# esp32_final.net
KiCad netlist of a schematic drawn in EasyEDA Pro
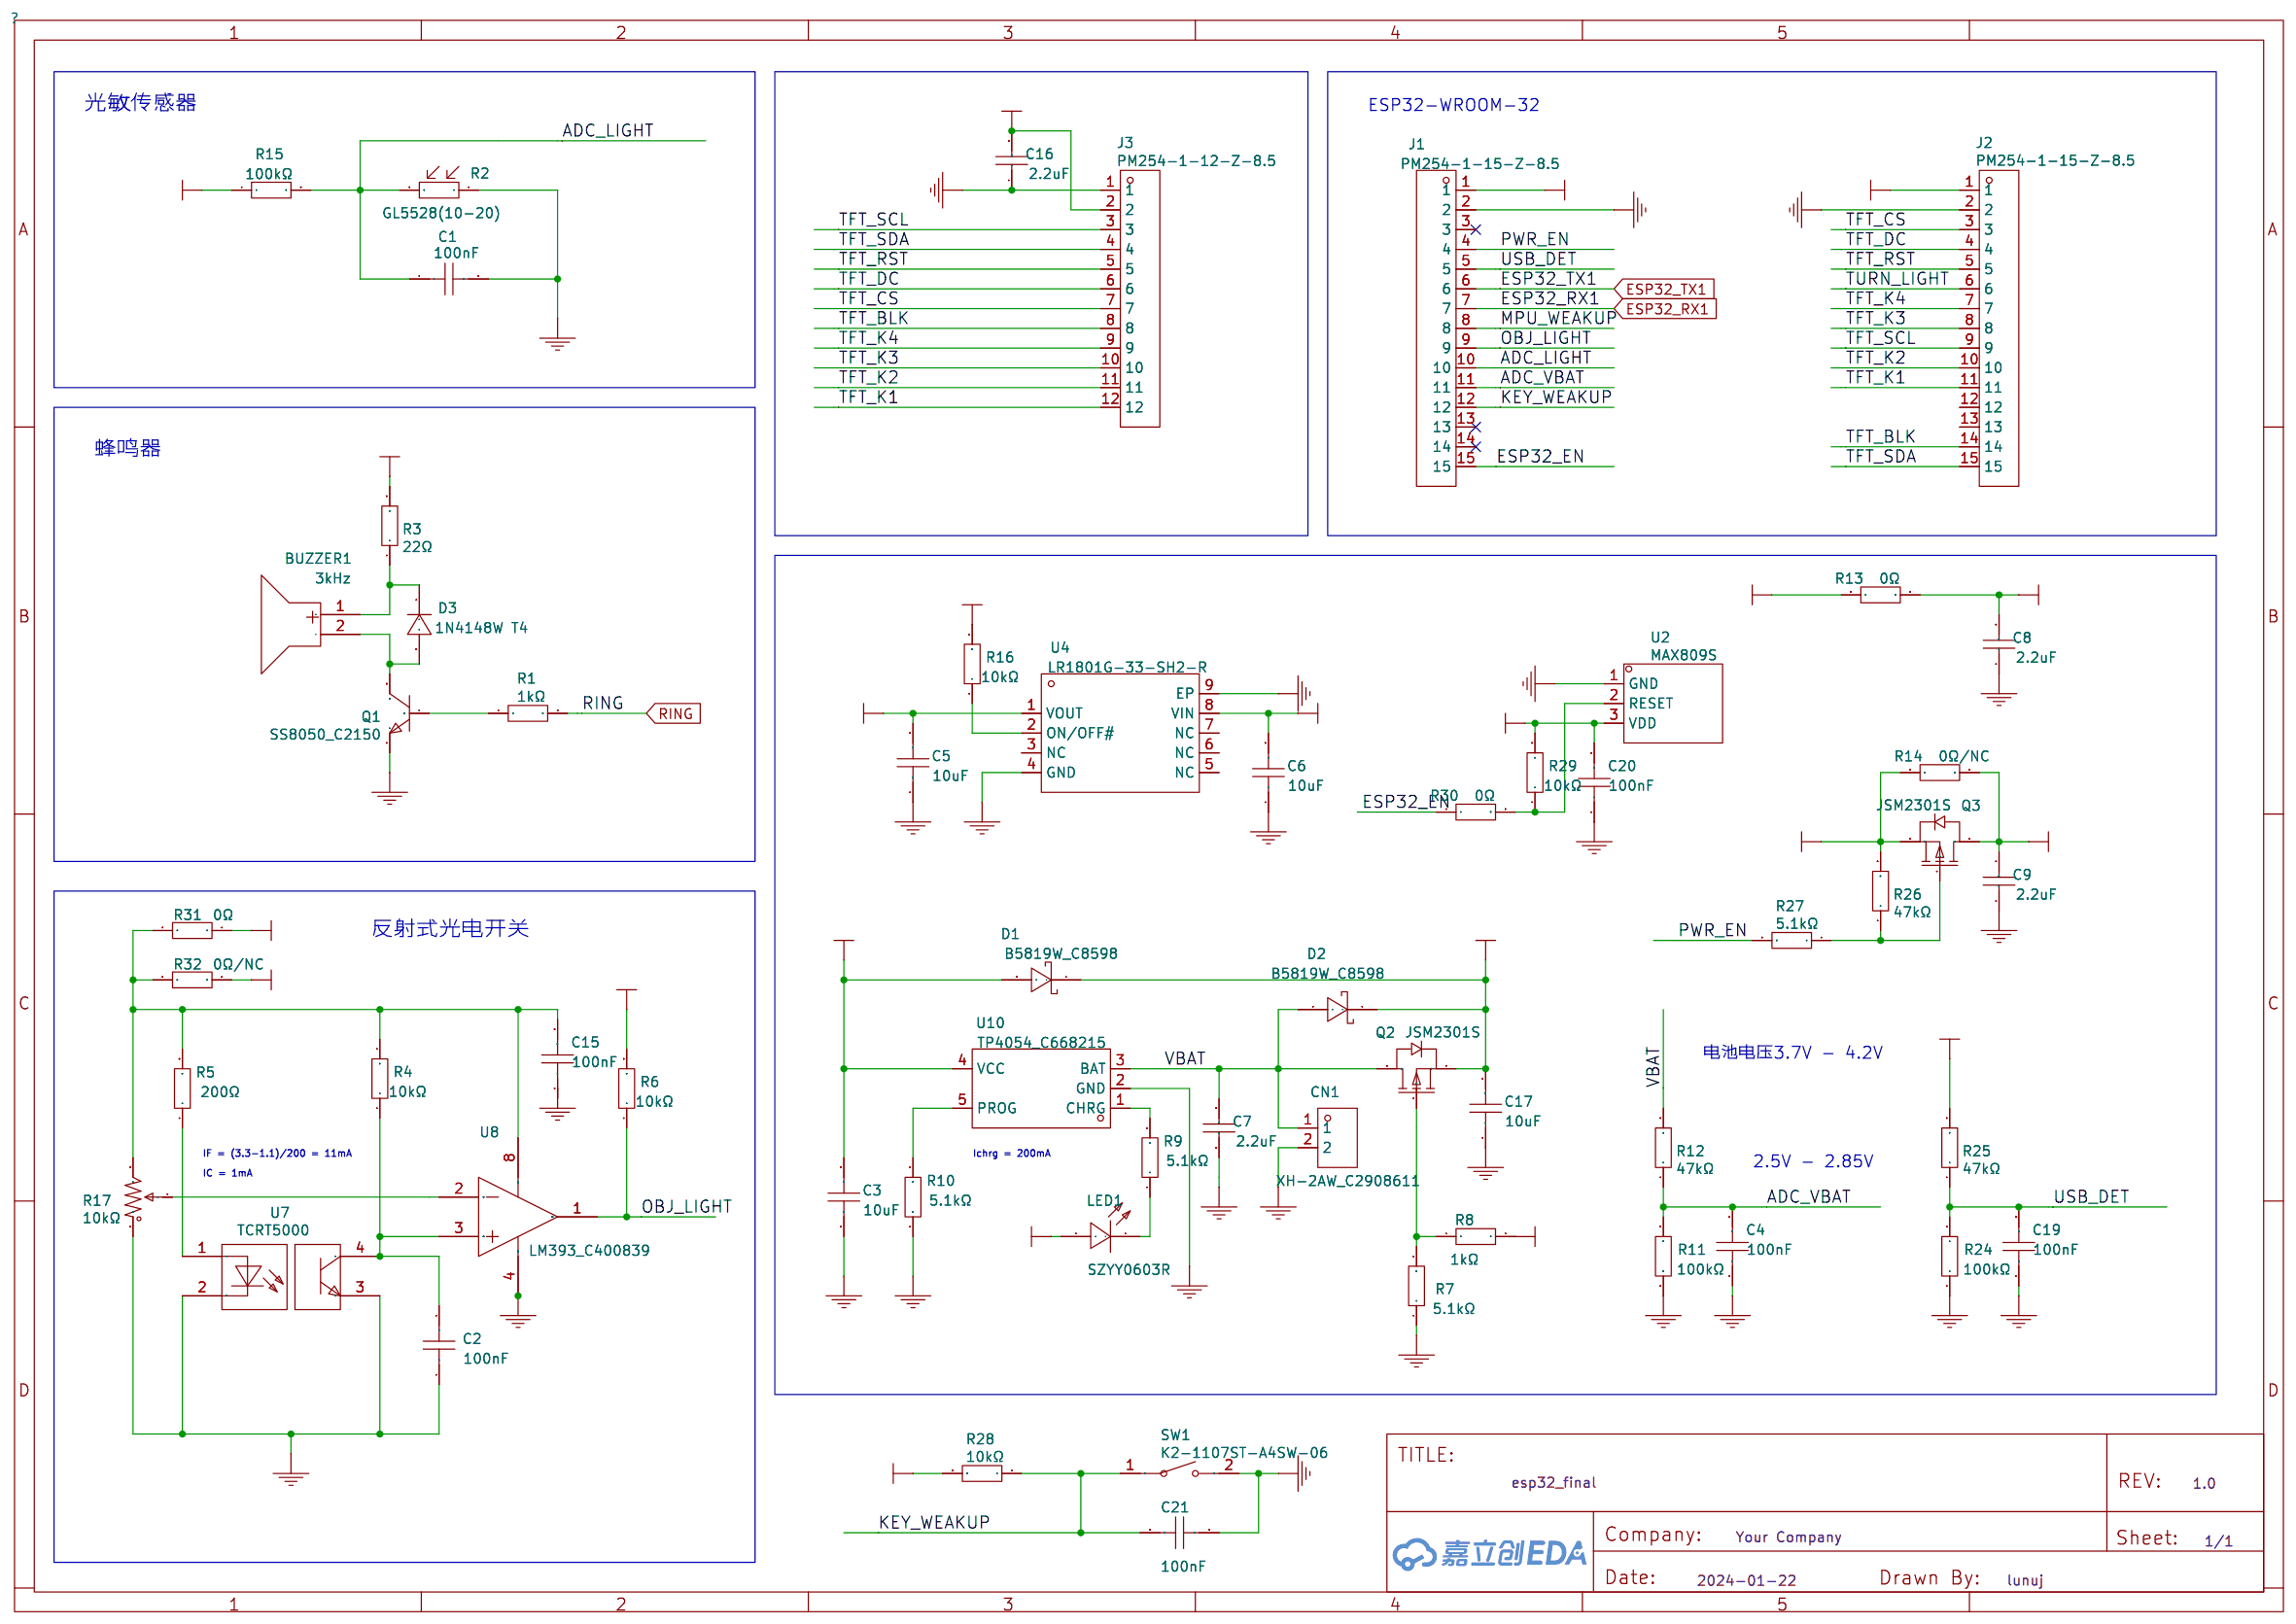
[diagram p0: ESP32]
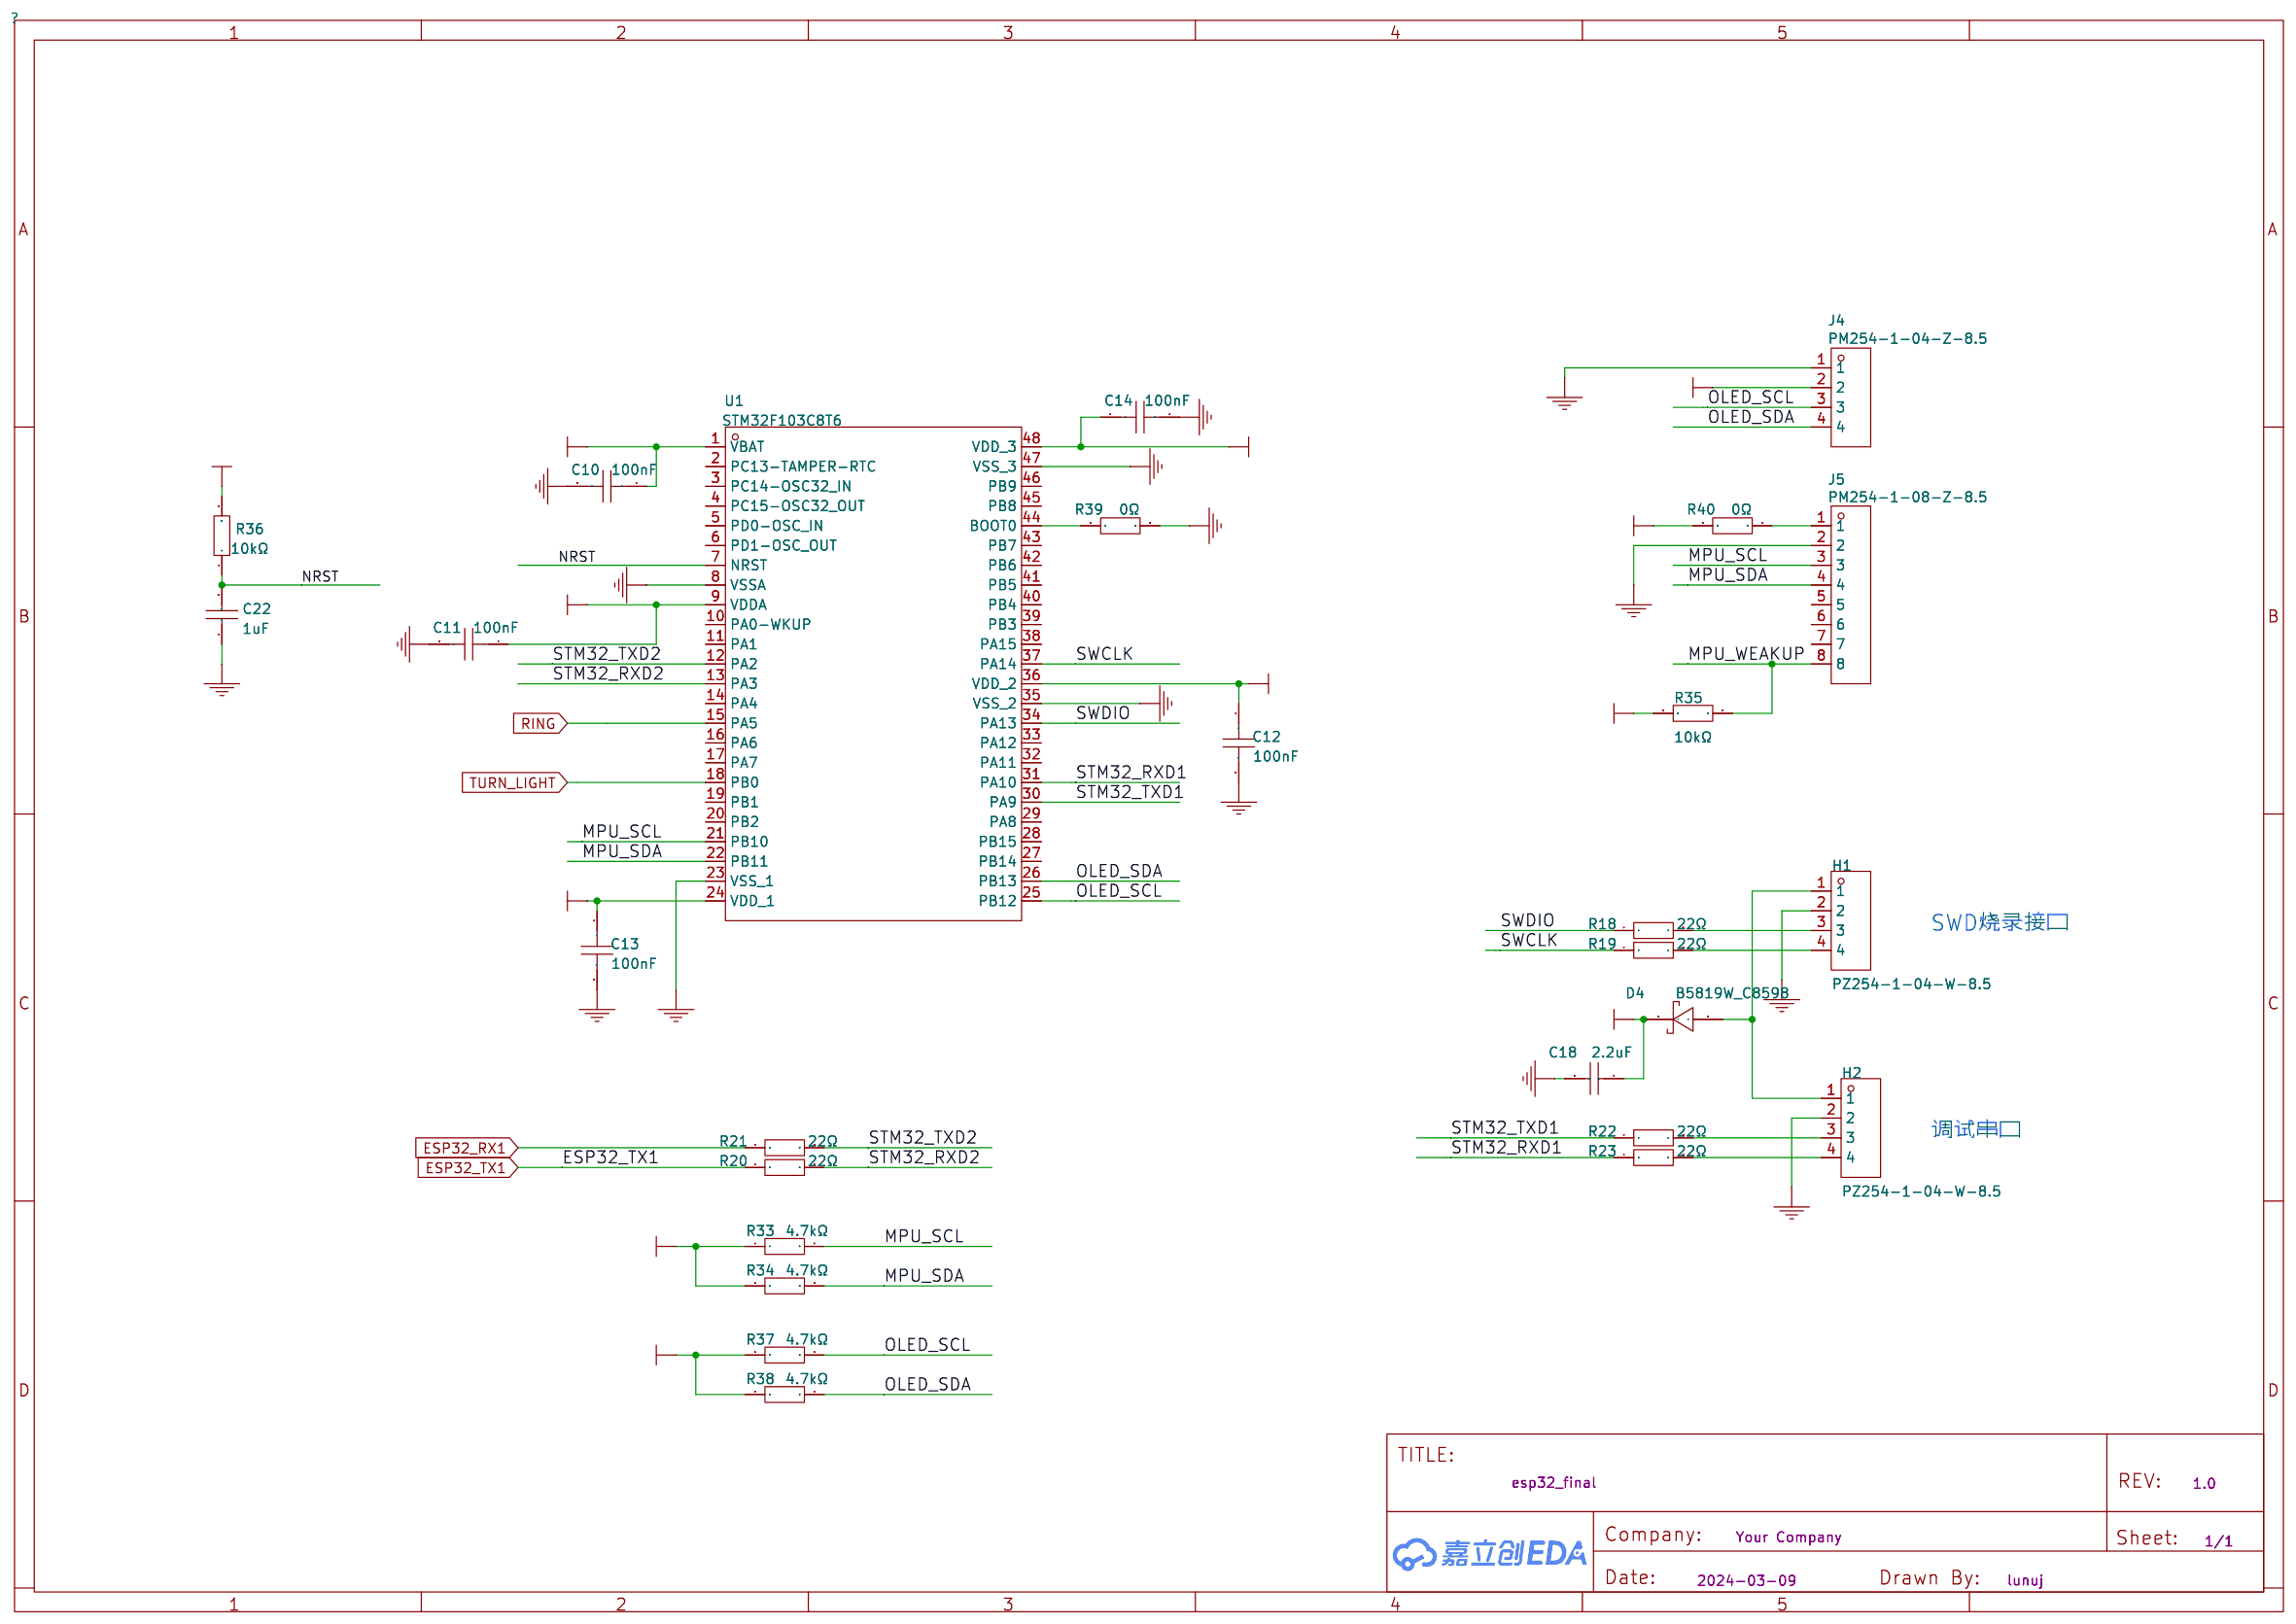
[diagram p1: STM32]

(export (version "E")
  (design (tool "Eeschema 10.0.6"))
  (components
    (comp (ref "BUZZER1")
      (value "3kHz")
      (footprint "easyedapro:footprint_b725")
      (fields (field (name "Manufacturer Part") "HNB09A03") (field (name "Manufacturer") "华能"))
      (libsource (lib "easyedapro") (part "3kHz"))
    )
    (comp (ref "C1")
      (value "100nF")
      (footprint "easyedapro:footprint_9e9b")
      (fields
        (field (name "Manufacturer Part") "CL10B104KB8NNNC")
        (field (name "Manufacturer") "SAMSUNG(三星)")
      )
      (libsource (lib "easyedapro") (part "100nF"))
    )
    (comp (ref "C2")
      (value "100nF")
      (footprint "easyedapro:footprint_9e9b")
      (fields
        (field (name "Manufacturer Part") "CL10B104KB8NNNC")
        (field (name "Manufacturer") "SAMSUNG(三星)")
      )
      (libsource (lib "easyedapro") (part "100nF"))
    )
    (comp (ref "C3")
      (value "10uF")
      (footprint "easyedapro:footprint_9e9b")
      (fields
        (field (name "Manufacturer Part") "CL10A106KP8NNNC")
        (field (name "Manufacturer") "SAMSUNG(三星)")
      )
      (libsource (lib "easyedapro") (part "10uF"))
    )
    (comp (ref "C4")
      (value "100nF")
      (footprint "easyedapro:footprint_9e9b")
      (fields
        (field (name "Manufacturer Part") "CL10B104KB8NNNC")
        (field (name "Manufacturer") "SAMSUNG(三星)")
      )
      (libsource (lib "easyedapro") (part "100nF"))
    )
    (comp (ref "C5")
      (value "10uF")
      (footprint "easyedapro:footprint_9e9b")
      (fields
        (field (name "Manufacturer Part") "CL10A106KP8NNNC")
        (field (name "Manufacturer") "SAMSUNG(三星)")
      )
      (libsource (lib "easyedapro") (part "10uF"))
    )
    (comp (ref "C6")
      (value "10uF")
      (footprint "easyedapro:footprint_9e9b")
      (fields
        (field (name "Manufacturer Part") "CL10A106KP8NNNC")
        (field (name "Manufacturer") "SAMSUNG(三星)")
      )
      (libsource (lib "easyedapro") (part "10uF"))
    )
    (comp (ref "C7")
      (value "2.2uF")
      (footprint "easyedapro:footprint_9e9b")
      (fields
        (field (name "Manufacturer Part") "CL10A225KP8NNNC")
        (field (name "Manufacturer") "SAMSUNG(三星)")
      )
      (libsource (lib "easyedapro") (part "2.2uF"))
    )
    (comp (ref "C8")
      (value "2.2uF")
      (footprint "easyedapro:footprint_9e9b")
      (fields
        (field (name "Manufacturer Part") "CL10A225KP8NNNC")
        (field (name "Manufacturer") "SAMSUNG(三星)")
      )
      (libsource (lib "easyedapro") (part "2.2uF"))
    )
    (comp (ref "C9")
      (value "2.2uF")
      (footprint "easyedapro:footprint_9e9b")
      (fields
        (field (name "Manufacturer Part") "CL10A225KP8NNNC")
        (field (name "Manufacturer") "SAMSUNG(三星)")
      )
      (libsource (lib "easyedapro") (part "2.2uF"))
    )
    (comp (ref "C15")
      (value "100nF")
      (footprint "easyedapro:footprint_9e9b")
      (fields
        (field (name "Manufacturer Part") "CL10B104KB8NNNC")
        (field (name "Manufacturer") "SAMSUNG(三星)")
      )
      (libsource (lib "easyedapro") (part "100nF"))
    )
    (comp (ref "C16")
      (value "2.2uF")
      (footprint "easyedapro:footprint_9e9b")
      (fields
        (field (name "Manufacturer Part") "CL10A225KP8NNNC")
        (field (name "Manufacturer") "SAMSUNG(三星)")
      )
      (libsource (lib "easyedapro") (part "2.2uF"))
    )
    (comp (ref "C17")
      (value "10uF")
      (footprint "easyedapro:footprint_9e9b")
      (fields
        (field (name "Manufacturer Part") "CL10A106KP8NNNC")
        (field (name "Manufacturer") "SAMSUNG(三星)")
      )
      (libsource (lib "easyedapro") (part "10uF"))
    )
    (comp (ref "C19")
      (value "100nF")
      (footprint "easyedapro:footprint_9e9b")
      (fields
        (field (name "Manufacturer Part") "CL10B104KB8NNNC")
        (field (name "Manufacturer") "SAMSUNG(三星)")
      )
      (libsource (lib "easyedapro") (part "100nF"))
    )
    (comp (ref "C20")
      (value "100nF")
      (footprint "easyedapro:footprint_9e9b")
      (fields
        (field (name "Manufacturer Part") "CL10B104KB8NNNC")
        (field (name "Manufacturer") "SAMSUNG(三星)")
      )
      (libsource (lib "easyedapro") (part "100nF"))
    )
    (comp (ref "C21")
      (value "100nF")
      (footprint "easyedapro:footprint_9e9b")
      (fields
        (field (name "Manufacturer Part") "CL10B104KB8NNNC")
        (field (name "Manufacturer") "SAMSUNG(三星)")
      )
      (libsource (lib "easyedapro") (part "100nF"))
    )
    (comp (ref "CN1")
      (value "XH-2AW_C2908611")
      (footprint "easyedapro:footprint_45c2")
      (fields (field (name "Manufacturer Part") "XH-2AW") (field (name "Manufacturer") "HCTL(华灿天禄)"))
      (libsource (lib "easyedapro") (part "XH-2AW_C2908611"))
    )
    (comp (ref "D1")
      (value "B5819W_C8598")
      (footprint "easyedapro:footprint_217f")
      (fields (field (name "Manufacturer Part") "B5819W SL") (field (name "Manufacturer") "CJ(江苏长电/长晶)"))
      (libsource (lib "easyedapro") (part "B5819W_C8598"))
    )
    (comp (ref "D2")
      (value "B5819W_C8598")
      (footprint "easyedapro:footprint_217f")
      (fields (field (name "Manufacturer Part") "B5819W SL") (field (name "Manufacturer") "CJ(江苏长电/长晶)"))
      (libsource (lib "easyedapro") (part "B5819W_C8598"))
    )
    (comp (ref "D3")
      (value "1N4148W T4")
      (footprint "easyedapro:footprint_2996")
      (fields (field (name "Manufacturer Part") "1N4148W") (field (name "Manufacturer") "CJ(江苏长电/长晶)"))
      (libsource (lib "easyedapro") (part "1N4148W T4"))
    )
    (comp (ref "J1")
      (value "PM254-1-15-Z-8.5")
      (footprint "easyedapro:footprint_1582")
      (fields (field (name "Manufacturer") "HCTL(华灿天禄)"))
      (libsource (lib "easyedapro") (part "PM254-1-15-Z-8.5"))
    )
    (comp (ref "J2")
      (value "PM254-1-15-Z-8.5")
      (footprint "easyedapro:footprint_1582")
      (fields (field (name "Manufacturer") "HCTL(华灿天禄)"))
      (libsource (lib "") (part "PM254-1-15-Z-8.5_1"))
    )
    (comp (ref "J3")
      (value "PM254-1-12-Z-8.5")
      (footprint "easyedapro:footprint_c90a")
      (fields (field (name "Manufacturer") "HCTL(华灿天禄)"))
      (libsource (lib "easyedapro") (part "PM254-1-12-Z-8.5"))
    )
    (comp (ref "LED1")
      (value "SZYY0603R")
      (footprint "easyedapro:footprint_3a94")
      (fields (field (name "Manufacturer") "yongyu(永裕光电)"))
      (libsource (lib "easyedapro") (part "SZYY0603R"))
    )
    (comp (ref "Q1")
      (value "SS8050_C2150")
      (footprint "easyedapro:footprint_40fb")
      (fields (field (name "Manufacturer Part") "SS8050") (field (name "Manufacturer") "CJ(江苏长电/长晶)"))
      (libsource (lib "easyedapro") (part "SS8050_C2150"))
    )
    (comp (ref "Q2")
      (value "JSM2301S")
      (footprint "easyedapro:footprint_40fb")
      (fields (field (name "Manufacturer") "JSMSEMI(杰盛微)"))
      (libsource (lib "easyedapro") (part "JSM2301S"))
    )
    (comp (ref "Q3")
      (value "JSM2301S")
      (footprint "easyedapro:footprint_40fb")
      (fields (field (name "Manufacturer") "JSMSEMI(杰盛微)"))
      (libsource (lib "") (part "JSM2301S_1"))
    )
    (comp (ref "R1")
      (value "1kΩ")
      (footprint "easyedapro:footprint_ff81")
      (fields (field (name "Manufacturer Part") "RC0603FR-071KL") (field (name "Manufacturer") "YAGEO(国巨)"))
      (libsource (lib "easyedapro") (part "1kΩ"))
    )
    (comp (ref "R2")
      (value "GL5528(10-20)")
      (footprint "easyedapro:footprint_7788")
      (fields (field (name "Manufacturer") "JCHL(晶创和立)"))
      (libsource (lib "easyedapro") (part "GL5528(10-20)"))
    )
    (comp (ref "R3")
      (value "22Ω")
      (footprint "easyedapro:footprint_ff81")
      (fields
        (field (name "Manufacturer Part") "0603WAF220JT5E")
        (field (name "Manufacturer") "UNI-ROYAL(厚声)")
      )
      (libsource (lib "easyedapro") (part "22Ω"))
    )
    (comp (ref "R4")
      (value "10kΩ")
      (footprint "easyedapro:footprint_ff81")
      (fields
        (field (name "Manufacturer Part") "0603WAF1002T5E")
        (field (name "Manufacturer") "UNI-ROYAL(厚声)")
      )
      (libsource (lib "easyedapro") (part "10kΩ"))
    )
    (comp (ref "R5")
      (value "200Ω")
      (footprint "easyedapro:footprint_ff81")
      (fields
        (field (name "Manufacturer Part") "0603WAJ0201T5E")
        (field (name "Manufacturer") "UNI-ROYAL(厚声)")
      )
      (libsource (lib "easyedapro") (part "200Ω"))
    )
    (comp (ref "R6")
      (value "10kΩ")
      (footprint "easyedapro:footprint_ff81")
      (fields
        (field (name "Manufacturer Part") "0603WAF1002T5E")
        (field (name "Manufacturer") "UNI-ROYAL(厚声)")
      )
      (libsource (lib "easyedapro") (part "10kΩ"))
    )
    (comp (ref "R7")
      (value "5.1kΩ")
      (footprint "easyedapro:footprint_ff81")
      (fields
        (field (name "Manufacturer Part") "0603WAF5101T5E")
        (field (name "Manufacturer") "UNI-ROYAL(厚声)")
      )
      (libsource (lib "easyedapro") (part "5.1kΩ"))
    )
    (comp (ref "R8")
      (value "1kΩ")
      (footprint "easyedapro:footprint_ff81")
      (fields (field (name "Manufacturer Part") "RC0603FR-071KL") (field (name "Manufacturer") "YAGEO(国巨)"))
      (libsource (lib "easyedapro") (part "1kΩ"))
    )
    (comp (ref "R9")
      (value "5.1kΩ")
      (footprint "easyedapro:footprint_ff81")
      (fields
        (field (name "Manufacturer Part") "0603WAF5101T5E")
        (field (name "Manufacturer") "UNI-ROYAL(厚声)")
      )
      (libsource (lib "easyedapro") (part "5.1kΩ"))
    )
    (comp (ref "R10")
      (value "5.1kΩ")
      (footprint "easyedapro:footprint_ff81")
      (fields
        (field (name "Manufacturer Part") "0603WAF5101T5E")
        (field (name "Manufacturer") "UNI-ROYAL(厚声)")
      )
      (libsource (lib "easyedapro") (part "5.1kΩ"))
    )
    (comp (ref "R11")
      (value "100kΩ")
      (footprint "easyedapro:footprint_ff81")
      (fields (field (name "Manufacturer Part") "RC0603FR-07100KL") (field (name "Manufacturer") "YAGEO(国巨)"))
      (libsource (lib "easyedapro") (part "100kΩ"))
    )
    (comp (ref "R12")
      (value "47kΩ")
      (footprint "easyedapro:footprint_ff81")
      (fields
        (field (name "Manufacturer Part") "0603WAF4702T5E")
        (field (name "Manufacturer") "UNI-ROYAL(厚声)")
      )
      (libsource (lib "easyedapro") (part "47kΩ"))
    )
    (comp (ref "R13")
      (value "0Ω")
      (footprint "easyedapro:footprint_ff81")
      (fields
        (field (name "Manufacturer Part") "0603WAF0000T5E")
        (field (name "Manufacturer") "UNI-ROYAL(厚声)")
      )
      (libsource (lib "easyedapro") (part "0Ω"))
    )
    (comp (ref "R14")
      (value "0Ω/NC")
      (footprint "easyedapro:footprint_ff81")
      (fields
        (field (name "Manufacturer Part") "0603WAF0000T5E")
        (field (name "Manufacturer") "UNI-ROYAL(厚声)")
      )
      (libsource (lib "easyedapro") (part "0Ω/NC"))
    )
    (comp (ref "R15")
      (value "100kΩ")
      (footprint "easyedapro:footprint_ff81")
      (fields (field (name "Manufacturer Part") "RC0603FR-07100KL") (field (name "Manufacturer") "YAGEO(国巨)"))
      (libsource (lib "easyedapro") (part "100kΩ"))
    )
    (comp (ref "R16")
      (value "10kΩ")
      (footprint "easyedapro:footprint_ff81")
      (fields
        (field (name "Manufacturer Part") "0603WAF1002T5E")
        (field (name "Manufacturer") "UNI-ROYAL(厚声)")
      )
      (libsource (lib "easyedapro") (part "10kΩ"))
    )
    (comp (ref "R17")
      (value "10kΩ")
      (footprint "easyedapro:footprint_5b8b")
      (fields (field (name "Manufacturer Part") "3362P-1-103") (field (name "Manufacturer") "BOCHEN(博晨)"))
      (libsource (lib "") (part "10kΩ_1"))
    )
    (comp (ref "R24")
      (value "100kΩ")
      (footprint "easyedapro:footprint_ff81")
      (fields (field (name "Manufacturer Part") "RC0603FR-07100KL") (field (name "Manufacturer") "YAGEO(国巨)"))
      (libsource (lib "easyedapro") (part "100kΩ"))
    )
    (comp (ref "R25")
      (value "47kΩ")
      (footprint "easyedapro:footprint_ff81")
      (fields
        (field (name "Manufacturer Part") "0603WAF4702T5E")
        (field (name "Manufacturer") "UNI-ROYAL(厚声)")
      )
      (libsource (lib "easyedapro") (part "47kΩ"))
    )
    (comp (ref "R26")
      (value "47kΩ")
      (footprint "easyedapro:footprint_ff81")
      (fields
        (field (name "Manufacturer Part") "0603WAF4702T5E")
        (field (name "Manufacturer") "UNI-ROYAL(厚声)")
      )
      (libsource (lib "easyedapro") (part "47kΩ"))
    )
    (comp (ref "R27")
      (value "5.1kΩ")
      (footprint "easyedapro:footprint_ff81")
      (fields
        (field (name "Manufacturer Part") "0603WAF5101T5E")
        (field (name "Manufacturer") "UNI-ROYAL(厚声)")
      )
      (libsource (lib "easyedapro") (part "5.1kΩ"))
    )
    (comp (ref "R28")
      (value "10kΩ")
      (footprint "easyedapro:footprint_ff81")
      (fields
        (field (name "Manufacturer Part") "0603WAF1002T5E")
        (field (name "Manufacturer") "UNI-ROYAL(厚声)")
      )
      (libsource (lib "easyedapro") (part "10kΩ"))
    )
    (comp (ref "R29")
      (value "10kΩ")
      (footprint "easyedapro:footprint_ff81")
      (fields
        (field (name "Manufacturer Part") "0603WAF1002T5E")
        (field (name "Manufacturer") "UNI-ROYAL(厚声)")
      )
      (libsource (lib "easyedapro") (part "10kΩ"))
    )
    (comp (ref "R30")
      (value "0Ω")
      (footprint "easyedapro:footprint_ff81")
      (fields
        (field (name "Manufacturer Part") "0603WAF0000T5E")
        (field (name "Manufacturer") "UNI-ROYAL(厚声)")
      )
      (libsource (lib "easyedapro") (part "0Ω"))
    )
    (comp (ref "R31")
      (value "0Ω")
      (footprint "easyedapro:footprint_ff81")
      (fields
        (field (name "Manufacturer Part") "0603WAF0000T5E")
        (field (name "Manufacturer") "UNI-ROYAL(厚声)")
      )
      (libsource (lib "easyedapro") (part "0Ω"))
    )
    (comp (ref "R32")
      (value "0Ω/NC")
      (footprint "easyedapro:footprint_ff81")
      (fields
        (field (name "Manufacturer Part") "0603WAF0000T5E")
        (field (name "Manufacturer") "UNI-ROYAL(厚声)")
      )
      (libsource (lib "easyedapro") (part "0Ω"))
    )
    (comp (ref "SW1")
      (value "K2-1107ST-A4SW-06")
      (footprint "easyedapro:footprint_5031")
      (fields (field (name "Manufacturer Part") "K2-1107ST-A4DW-06") (field (name "Manufacturer") "韩国韩荣"))
      (libsource (lib "easyedapro") (part "K2-1107ST-A4SW-06"))
    )
    (comp (ref "U2")
      (value "MAX809S")
      (footprint "easyedapro:footprint_40fb")
      (fields (field (name "Manufacturer") "UMW(友台半导体)"))
      (libsource (lib "easyedapro") (part "MAX809S"))
    )
    (comp (ref "U4")
      (value "LR1801G-33-SH2-R")
      (footprint "easyedapro:footprint_c089")
      (fields (field (name "Manufacturer") "UTC(友顺)"))
      (libsource (lib "easyedapro") (part "LR1801G-33-SH2-R"))
    )
    (comp (ref "U7")
      (value "TCRT5000")
      (footprint "easyedapro:footprint_17ac")
      (fields (field (name "Manufacturer") "VISHAY(威世)"))
      (libsource (lib "easyedapro") (part "TCRT5000"))
    )
    (comp (ref "U8")
      (value "LM393_C400839")
      (footprint "easyedapro:footprint_6934")
      (fields (field (name "Manufacturer Part") "LM393") (field (name "Manufacturer") "IDCHIP(英锐芯)"))
      (libsource (lib "easyedapro") (part "LM393_C400839"))
    )
    (comp (ref "U10")
      (value "TP4054_C668215")
      (footprint "easyedapro:footprint_0cd8")
      (fields (field (name "Manufacturer Part") "TP4054") (field (name "Manufacturer") "UMW(友台半导体)"))
      (libsource (lib "easyedapro") (part "TP4054_C668215"))
    )
    (comp (ref "C10")
      (value "100nF")
      (footprint "easyedapro:footprint_9e9b")
      (fields
        (field (name "Manufacturer Part") "CL10B104KB8NNNC")
        (field (name "Manufacturer") "SAMSUNG(三星)")
      )
      (libsource (lib "easyedapro") (part "100nF"))
    )
    (comp (ref "C11")
      (value "100nF")
      (footprint "easyedapro:footprint_9e9b")
      (fields
        (field (name "Manufacturer Part") "CL10B104KB8NNNC")
        (field (name "Manufacturer") "SAMSUNG(三星)")
      )
      (libsource (lib "easyedapro") (part "100nF"))
    )
    (comp (ref "C12")
      (value "100nF")
      (footprint "easyedapro:footprint_9e9b")
      (fields
        (field (name "Manufacturer Part") "CL10B104KB8NNNC")
        (field (name "Manufacturer") "SAMSUNG(三星)")
      )
      (libsource (lib "easyedapro") (part "100nF"))
    )
    (comp (ref "C13")
      (value "100nF")
      (footprint "easyedapro:footprint_9e9b")
      (fields
        (field (name "Manufacturer Part") "CL10B104KB8NNNC")
        (field (name "Manufacturer") "SAMSUNG(三星)")
      )
      (libsource (lib "easyedapro") (part "100nF"))
    )
    (comp (ref "C14")
      (value "100nF")
      (footprint "easyedapro:footprint_9e9b")
      (fields
        (field (name "Manufacturer Part") "CL10B104KB8NNNC")
        (field (name "Manufacturer") "SAMSUNG(三星)")
      )
      (libsource (lib "easyedapro") (part "100nF"))
    )
    (comp (ref "C18")
      (value "2.2uF")
      (footprint "easyedapro:footprint_9e9b")
      (fields
        (field (name "Manufacturer Part") "CL10A225KP8NNNC")
        (field (name "Manufacturer") "SAMSUNG(三星)")
      )
      (libsource (lib "easyedapro") (part "2.2uF"))
    )
    (comp (ref "C22")
      (value "1uF")
      (footprint "easyedapro:C0603")
      (description "容值:1uF;精度:±10%;额定电压:16V;材质(温度系数):X5R;")
      (fields
        (field (name "Manufacturer Part") "CL10A105KO8NNNC")
        (field (name "Manufacturer") "SAMSUNG(三星)")
      )
      (libsource (lib "easyedapro") (part "CL10A105KO8NNNC"))
    )
    (comp (ref "D4")
      (value "B5819W_C8598")
      (footprint "easyedapro:footprint_217f")
      (fields (field (name "Manufacturer Part") "B5819W SL") (field (name "Manufacturer") "CJ(江苏长电/长晶)"))
      (libsource (lib "easyedapro") (part "B5819W_C8598"))
    )
    (comp (ref "H1")
      (value "PZ254-1-04-W-8.5")
      (footprint "easyedapro:HDR-TH_04P-P2.54-H-M-W10.4-N")
      (fields (field (name "Manufacturer") "HCTL(华灿天禄)"))
      (libsource (lib "easyedapro") (part "PZ254-1-04-W-8.5"))
    )
    (comp (ref "H2")
      (value "PZ254-1-04-W-8.5")
      (footprint "easyedapro:HDR-TH_04P-P2.54-H-M-W10.4-N")
      (fields (field (name "Manufacturer") "HCTL(华灿天禄)"))
      (libsource (lib "easyedapro") (part "PZ254-1-04-W-8.5"))
    )
    (comp (ref "J4")
      (value "PM254-1-04-Z-8.5")
      (footprint "easyedapro:footprint_a6c7")
      (fields (field (name "Manufacturer") "HCTL(华灿天禄)"))
      (libsource (lib "easyedapro") (part "PM254-1-04-Z-8.5"))
    )
    (comp (ref "J5")
      (value "PM254-1-08-Z-8.5")
      (footprint "easyedapro:footprint_d2a7")
      (fields (field (name "Manufacturer") "HCTL(华灿天禄)"))
      (libsource (lib "easyedapro") (part "PM254-1-08-Z-8.5"))
    )
    (comp (ref "R18")
      (value "22Ω")
      (footprint "easyedapro:footprint_ff81")
      (fields
        (field (name "Manufacturer Part") "0603WAF220JT5E")
        (field (name "Manufacturer") "UNI-ROYAL(厚声)")
      )
      (libsource (lib "easyedapro") (part "22Ω"))
    )
    (comp (ref "R19")
      (value "22Ω")
      (footprint "easyedapro:footprint_ff81")
      (fields
        (field (name "Manufacturer Part") "0603WAF220JT5E")
        (field (name "Manufacturer") "UNI-ROYAL(厚声)")
      )
      (libsource (lib "easyedapro") (part "22Ω"))
    )
    (comp (ref "R20")
      (value "22Ω")
      (footprint "easyedapro:footprint_ff81")
      (fields
        (field (name "Manufacturer Part") "0603WAF220JT5E")
        (field (name "Manufacturer") "UNI-ROYAL(厚声)")
      )
      (libsource (lib "easyedapro") (part "22Ω"))
    )
    (comp (ref "R21")
      (value "22Ω")
      (footprint "easyedapro:footprint_ff81")
      (fields
        (field (name "Manufacturer Part") "0603WAF220JT5E")
        (field (name "Manufacturer") "UNI-ROYAL(厚声)")
      )
      (libsource (lib "easyedapro") (part "22Ω"))
    )
    (comp (ref "R22")
      (value "22Ω")
      (footprint "easyedapro:footprint_ff81")
      (fields
        (field (name "Manufacturer Part") "0603WAF220JT5E")
        (field (name "Manufacturer") "UNI-ROYAL(厚声)")
      )
      (libsource (lib "easyedapro") (part "22Ω"))
    )
    (comp (ref "R23")
      (value "22Ω")
      (footprint "easyedapro:footprint_ff81")
      (fields
        (field (name "Manufacturer Part") "0603WAF220JT5E")
        (field (name "Manufacturer") "UNI-ROYAL(厚声)")
      )
      (libsource (lib "easyedapro") (part "22Ω"))
    )
    (comp (ref "R33")
      (value "4.7kΩ")
      (footprint "easyedapro:R0603")
      (description "电阻类型:厚膜电阻;阻值:4.7kΩ;精度:±1%;功率:100mW;最大工作电压:75V;温度系数:±100ppm/°C;")
      (fields
        (field (name "Manufacturer Part") "0603WAF4701T5E")
        (field (name "Manufacturer") "UNI-ROYAL(厚声)")
      )
      (libsource (lib "easyedapro") (part "0603WAF4701T5E"))
    )
    (comp (ref "R34")
      (value "4.7kΩ")
      (footprint "easyedapro:R0603")
      (description "电阻类型:厚膜电阻;阻值:4.7kΩ;精度:±1%;功率:100mW;最大工作电压:75V;温度系数:±100ppm/°C;")
      (fields
        (field (name "Manufacturer Part") "0603WAF4701T5E")
        (field (name "Manufacturer") "UNI-ROYAL(厚声)")
      )
      (libsource (lib "easyedapro") (part "0603WAF4701T5E"))
    )
    (comp (ref "R35")
      (value "10kΩ")
      (footprint "easyedapro:footprint_ff81")
      (fields
        (field (name "Manufacturer Part") "0603WAF1002T5E")
        (field (name "Manufacturer") "UNI-ROYAL(厚声)")
      )
      (libsource (lib "easyedapro") (part "10kΩ"))
    )
    (comp (ref "R36")
      (value "10kΩ")
      (footprint "easyedapro:footprint_ff81")
      (fields
        (field (name "Manufacturer Part") "0603WAF1002T5E")
        (field (name "Manufacturer") "UNI-ROYAL(厚声)")
      )
      (libsource (lib "easyedapro") (part "10kΩ"))
    )
    (comp (ref "R37")
      (value "4.7kΩ")
      (footprint "easyedapro:R0603")
      (description "电阻类型:厚膜电阻;阻值:4.7kΩ;精度:±1%;功率:100mW;最大工作电压:75V;温度系数:±100ppm/°C;")
      (fields
        (field (name "Manufacturer Part") "0603WAF4701T5E")
        (field (name "Manufacturer") "UNI-ROYAL(厚声)")
      )
      (libsource (lib "easyedapro") (part "0603WAF4701T5E"))
    )
    (comp (ref "R38")
      (value "4.7kΩ")
      (footprint "easyedapro:R0603")
      (description "电阻类型:厚膜电阻;阻值:4.7kΩ;精度:±1%;功率:100mW;最大工作电压:75V;温度系数:±100ppm/°C;")
      (fields
        (field (name "Manufacturer Part") "0603WAF4701T5E")
        (field (name "Manufacturer") "UNI-ROYAL(厚声)")
      )
      (libsource (lib "easyedapro") (part "0603WAF4701T5E"))
    )
    (comp (ref "R39")
      (value "0Ω")
      (footprint "easyedapro:footprint_ff81")
      (fields
        (field (name "Manufacturer Part") "0603WAF0000T5E")
        (field (name "Manufacturer") "UNI-ROYAL(厚声)")
      )
      (libsource (lib "easyedapro") (part "0Ω"))
    )
    (comp (ref "R40")
      (value "0Ω")
      (footprint "easyedapro:footprint_ff81")
      (fields
        (field (name "Manufacturer Part") "0603WAF0000T5E")
        (field (name "Manufacturer") "UNI-ROYAL(厚声)")
      )
      (libsource (lib "easyedapro") (part "0Ω"))
    )
    (comp (ref "U1")
      (value "STM32F103C8T6")
      (footprint "easyedapro:footprint_1eac")
      (fields (field (name "Manufacturer") "ST(意法半导体)"))
      (libsource (lib "easyedapro") (part "STM32F103C8T6"))
    )
  )
  (nets
    (net (code "1") (name "ADC_LIGHT") (class "Default")
      (node (ref "C1") (pin "1") (pinfunction "1_1") (pintype "unspecified"))
      (node (ref "J1") (pin "10") (pinfunction "10_10") (pintype "unspecified"))
      (node (ref "R15") (pin "2") (pinfunction "2_2") (pintype "unspecified"))
      (node (ref "R2") (pin "2") (pinfunction "2_2") (pintype "input"))
    )
    (net (code "2") (name "ADC_VBAT") (class "Default")
      (node (ref "C4") (pin "2") (pinfunction "2_2") (pintype "unspecified"))
      (node (ref "J1") (pin "11") (pinfunction "11_11") (pintype "unspecified"))
      (node (ref "R11") (pin "2") (pinfunction "2_2") (pintype "unspecified"))
      (node (ref "R12") (pin "1") (pinfunction "1_1") (pintype "input"))
    )
    (net (code "3") (name "ESP32_EN") (class "Default")
      (node (ref "J1") (pin "15") (pinfunction "15_15") (pintype "unspecified"))
      (node (ref "R30") (pin "1") (pinfunction "1_1") (pintype "input"))
    )
    (net (code "4") (name "ESP32_RX1") (class "Default")
      (node (ref "J1") (pin "7") (pinfunction "7_7") (pintype "unspecified"))
      (node (ref "R21") (pin "1") (pinfunction "1_1") (pintype "input"))
    )
    (net (code "5") (name "ESP32_TX1") (class "Default")
      (node (ref "J1") (pin "6") (pinfunction "6_6") (pintype "unspecified"))
      (node (ref "R20") (pin "1") (pinfunction "1_1") (pintype "input"))
    )
    (net (code "6") (name "GND") (class "Default")
      (node (ref "C1") (pin "2") (pinfunction "2_2") (pintype "unspecified"))
      (node (ref "C10") (pin "2") (pinfunction "2_2") (pintype "unspecified"))
      (node (ref "C11") (pin "2") (pinfunction "2_2") (pintype "unspecified"))
      (node (ref "C12") (pin "2") (pinfunction "2_2") (pintype "unspecified"))
      (node (ref "C13") (pin "2") (pinfunction "2_2") (pintype "unspecified"))
      (node (ref "C14") (pin "1") (pinfunction "1_1") (pintype "unspecified"))
      (node (ref "C15") (pin "1") (pinfunction "1_1") (pintype "unspecified"))
      (node (ref "C16") (pin "1") (pinfunction "1_1") (pintype "input"))
      (node (ref "C17") (pin "1") (pinfunction "1_1") (pintype "unspecified"))
      (node (ref "C18") (pin "2") (pinfunction "2_2") (pintype "input"))
      (node (ref "C19") (pin "1") (pinfunction "1_1") (pintype "unspecified"))
      (node (ref "C2") (pin "1") (pinfunction "1_1") (pintype "unspecified"))
      (node (ref "C20") (pin "1") (pinfunction "1_1") (pintype "unspecified"))
      (node (ref "C21") (pin "1") (pinfunction "1_1") (pintype "unspecified"))
      (node (ref "C22") (pin "1") (pinfunction "1_1") (pintype "input"))
      (node (ref "C3") (pin "1") (pinfunction "1_1") (pintype "unspecified"))
      (node (ref "C4") (pin "1") (pinfunction "1_1") (pintype "unspecified"))
      (node (ref "C5") (pin "1") (pinfunction "1_1") (pintype "unspecified"))
      (node (ref "C6") (pin "1") (pinfunction "1_1") (pintype "unspecified"))
      (node (ref "C7") (pin "1") (pinfunction "1_1") (pintype "input"))
      (node (ref "C8") (pin "1") (pinfunction "1_1") (pintype "input"))
      (node (ref "C9") (pin "1") (pinfunction "1_1") (pintype "input"))
      (node (ref "CN1") (pin "2") (pinfunction "2_2") (pintype "unspecified"))
      (node (ref "H1") (pin "2") (pinfunction "2_2") (pintype "unspecified"))
      (node (ref "H2") (pin "2") (pinfunction "2_2") (pintype "unspecified"))
      (node (ref "J1") (pin "2") (pinfunction "2_2") (pintype "unspecified"))
      (node (ref "J2") (pin "2") (pinfunction "2_2") (pintype "unspecified"))
      (node (ref "J3") (pin "1") (pinfunction "1_1") (pintype "unspecified"))
      (node (ref "J4") (pin "1") (pinfunction "1_1") (pintype "unspecified"))
      (node (ref "J5") (pin "2") (pinfunction "2_2") (pintype "unspecified"))
      (node (ref "Q1") (pin "2") (pinfunction "E_2") (pintype "unspecified"))
      (node (ref "R10") (pin "1") (pinfunction "1_1") (pintype "input"))
      (node (ref "R11") (pin "1") (pinfunction "1_1") (pintype "unspecified"))
      (node (ref "R17") (pin "1") (pinfunction "1_1") (pintype "unspecified"))
      (node (ref "R2") (pin "1") (pinfunction "1_1") (pintype "input"))
      (node (ref "R24") (pin "1") (pinfunction "1_1") (pintype "unspecified"))
      (node (ref "R39") (pin "2") (pinfunction "2_2") (pintype "input"))
      (node (ref "R7") (pin "1") (pinfunction "1_1") (pintype "input"))
      (node (ref "SW1") (pin "2") (pinfunction "2_2") (pintype "unspecified"))
      (node (ref "U1") (pin "23") (pinfunction "VSS_1_23") (pintype "unspecified"))
      (node (ref "U1") (pin "35") (pinfunction "VSS_2_35") (pintype "unspecified"))
      (node (ref "U1") (pin "47") (pinfunction "VSS_3_47") (pintype "unspecified"))
      (node (ref "U1") (pin "8") (pinfunction "VSSA_8") (pintype "unspecified"))
      (node (ref "U10") (pin "2") (pinfunction "GND_2") (pintype "unspecified"))
      (node (ref "U2") (pin "1") (pinfunction "GND_1") (pintype "unspecified"))
      (node (ref "U4") (pin "4") (pinfunction "GND_4") (pintype "unspecified"))
      (node (ref "U4") (pin "9") (pinfunction "EP_9") (pintype "unspecified"))
      (node (ref "U7") (pin "2") (pinfunction "2_2") (pintype "unspecified"))
      (node (ref "U7") (pin "3") (pinfunction "3_3") (pintype "unspecified"))
      (node (ref "U8") (pin "4") (pinfunction "GND_4") (pintype "unspecified"))
    )
    (net (code "7") (name "KEY_WEAKUP") (class "Default")
      (node (ref "C21") (pin "2") (pinfunction "2_2") (pintype "unspecified"))
      (node (ref "J1") (pin "12") (pinfunction "12_12") (pintype "unspecified"))
      (node (ref "R28") (pin "1") (pinfunction "1_1") (pintype "input"))
      (node (ref "SW1") (pin "1") (pinfunction "1_1") (pintype "unspecified"))
    )
    (net (code "8") (name "MPU_SCL") (class "Default")
      (node (ref "J5") (pin "3") (pinfunction "3_3") (pintype "unspecified"))
      (node (ref "R33") (pin "2") (pinfunction "2_2") (pintype "input"))
      (node (ref "U1") (pin "21") (pinfunction "PB10_21") (pintype "unspecified"))
    )
    (net (code "9") (name "MPU_SDA") (class "Default")
      (node (ref "J5") (pin "4") (pinfunction "4_4") (pintype "unspecified"))
      (node (ref "R34") (pin "2") (pinfunction "2_2") (pintype "input"))
      (node (ref "U1") (pin "22") (pinfunction "PB11_22") (pintype "unspecified"))
    )
    (net (code "10") (name "MPU_WEAKUP") (class "Default")
      (node (ref "J1") (pin "8") (pinfunction "8_8") (pintype "unspecified"))
      (node (ref "J5") (pin "8") (pinfunction "8_8") (pintype "unspecified"))
      (node (ref "R35") (pin "1") (pinfunction "1_1") (pintype "input"))
    )
    (net (code "11") (name "NRST") (class "Default")
      (node (ref "C22") (pin "2") (pinfunction "2_2") (pintype "input"))
      (node (ref "R36") (pin "1") (pinfunction "1_1") (pintype "input"))
      (node (ref "U1") (pin "7") (pinfunction "NRST_7") (pintype "unspecified"))
    )
    (net (code "12") (name "Net-(BUZZER1-+)") (class "Default")
      (node (ref "BUZZER1") (pin "1") (pinfunction "+_1") (pintype "unspecified"))
      (node (ref "D3") (pin "1") (pinfunction "K_1") (pintype "unspecified"))
      (node (ref "R3") (pin "1") (pinfunction "1_1") (pintype "input"))
    )
    (net (code "13") (name "Net-(BUZZER1--)") (class "Default")
      (node (ref "BUZZER1") (pin "2") (pinfunction "-_2") (pintype "unspecified"))
      (node (ref "D3") (pin "2") (pinfunction "A_2") (pintype "unspecified"))
      (node (ref "Q1") (pin "3") (pinfunction "C_3") (pintype "unspecified"))
    )
    (net (code "14") (name "Net-(D4-+)") (class "Default")
      (node (ref "D4") (pin "2") (pinfunction "+_2") (pintype "unspecified"))
      (node (ref "H1") (pin "1") (pinfunction "1_1") (pintype "unspecified"))
      (node (ref "H2") (pin "1") (pinfunction "1_1") (pintype "unspecified"))
    )
    (net (code "15") (name "Net-(H1-Pad3)") (class "Default")
      (node (ref "H1") (pin "3") (pinfunction "3_3") (pintype "unspecified"))
      (node (ref "R18") (pin "2") (pinfunction "2_2") (pintype "input"))
    )
    (net (code "16") (name "Net-(H1-Pad4)") (class "Default")
      (node (ref "H1") (pin "4") (pinfunction "4_4") (pintype "unspecified"))
      (node (ref "R19") (pin "2") (pinfunction "2_2") (pintype "input"))
    )
    (net (code "17") (name "Net-(H2-Pad3)") (class "Default")
      (node (ref "H2") (pin "3") (pinfunction "3_3") (pintype "unspecified"))
      (node (ref "R22") (pin "2") (pinfunction "2_2") (pintype "input"))
    )
    (net (code "18") (name "Net-(H2-Pad4)") (class "Default")
      (node (ref "H2") (pin "4") (pinfunction "4_4") (pintype "unspecified"))
      (node (ref "R23") (pin "2") (pinfunction "2_2") (pintype "input"))
    )
    (net (code "19") (name "Net-(J5-Pad1)") (class "Default")
      (node (ref "J5") (pin "1") (pinfunction "1_1") (pintype "unspecified"))
      (node (ref "R40") (pin "2") (pinfunction "2_2") (pintype "input"))
    )
    (net (code "20") (name "Net-(LED1--)") (class "Default")
      (node (ref "LED1") (pin "2") (pinfunction "-_2") (pintype "unspecified"))
      (node (ref "R9") (pin "1") (pinfunction "1_1") (pintype "input"))
    )
    (net (code "21") (name "Net-(Q1-B)") (class "Default")
      (node (ref "Q1") (pin "1") (pinfunction "B_1") (pintype "unspecified"))
      (node (ref "R1") (pin "1") (pinfunction "1_1") (pintype "input"))
    )
    (net (code "22") (name "Net-(Q2-G)") (class "Default")
      (node (ref "Q2") (pin "1") (pinfunction "G_1") (pintype "unspecified"))
      (node (ref "R7") (pin "2") (pinfunction "2_2") (pintype "input"))
      (node (ref "R8") (pin "1") (pinfunction "1_1") (pintype "input"))
    )
    (net (code "23") (name "Net-(Q3-G)") (class "Default")
      (node (ref "Q3") (pin "1") (pinfunction "G_1") (pintype "unspecified"))
      (node (ref "R26") (pin "1") (pinfunction "1_1") (pintype "input"))
      (node (ref "R27") (pin "1") (pinfunction "1_1") (pintype "input"))
    )
    (net (code "24") (name "Net-(R5-Pad1)") (class "Default")
      (node (ref "R5") (pin "1") (pinfunction "1_1") (pintype "input"))
      (node (ref "U7") (pin "1") (pinfunction "1_1") (pintype "unspecified"))
    )
    (net (code "25") (name "Net-(U1-BOOT0)") (class "Default")
      (node (ref "R39") (pin "1") (pinfunction "1_1") (pintype "input"))
      (node (ref "U1") (pin "44") (pinfunction "BOOT0_44") (pintype "unspecified"))
    )
    (net (code "26") (name "Net-(U2-RESET)") (class "Default")
      (node (ref "R29") (pin "1") (pinfunction "1_1") (pintype "input"))
      (node (ref "R30") (pin "2") (pinfunction "2_2") (pintype "input"))
      (node (ref "U2") (pin "2") (pinfunction "RESET_2") (pintype "unspecified"))
    )
    (net (code "27") (name "Net-(U4-ON{slash}OFF#)") (class "Default")
      (node (ref "R16") (pin "1") (pinfunction "1_1") (pintype "input"))
      (node (ref "U4") (pin "2") (pinfunction "ON/OFF#_2") (pintype "unspecified"))
    )
    (net (code "28") (name "Net-(U8-INA+)") (class "Default")
      (node (ref "C2") (pin "2") (pinfunction "2_2") (pintype "unspecified"))
      (node (ref "R4") (pin "1") (pinfunction "1_1") (pintype "input"))
      (node (ref "U7") (pin "4") (pinfunction "4_4") (pintype "unspecified"))
      (node (ref "U8") (pin "3") (pinfunction "INA+_3") (pintype "unspecified"))
    )
    (net (code "29") (name "Net-(U8-INA-)") (class "Default")
      (node (ref "R17") (pin "2") (pinfunction "2_2") (pintype "unspecified"))
      (node (ref "U8") (pin "2") (pinfunction "INA-_2") (pintype "unspecified"))
    )
    (net (code "30") (name "Net-(U8-VCC)") (class "Default")
      (node (ref "C15") (pin "2") (pinfunction "2_2") (pintype "unspecified"))
      (node (ref "R17") (pin "3") (pinfunction "3_3") (pintype "unspecified"))
      (node (ref "R31") (pin "2") (pinfunction "2_2") (pintype "input"))
      (node (ref "R32") (pin "2") (pinfunction "2_2") (pintype "input"))
      (node (ref "R4") (pin "2") (pinfunction "2_2") (pintype "input"))
      (node (ref "R5") (pin "2") (pinfunction "2_2") (pintype "input"))
      (node (ref "U8") (pin "8") (pinfunction "VCC_8") (pintype "unspecified"))
    )
    (net (code "31") (name "Net-(U10-CHRG)") (class "Default")
      (node (ref "R9") (pin "2") (pinfunction "2_2") (pintype "input"))
      (node (ref "U10") (pin "1") (pinfunction "CHRG_1") (pintype "unspecified"))
    )
    (net (code "32") (name "Net-(U10-PROG)") (class "Default")
      (node (ref "R10") (pin "2") (pinfunction "2_2") (pintype "input"))
      (node (ref "U10") (pin "5") (pinfunction "PROG_5") (pintype "unspecified"))
    )
    (net (code "33") (name "OBJ_LIGHT") (class "Default")
      (node (ref "J1") (pin "9") (pinfunction "9_9") (pintype "unspecified"))
      (node (ref "R6") (pin "1") (pinfunction "1_1") (pintype "input"))
      (node (ref "U8") (pin "1") (pinfunction "OUTA_1") (pintype "output"))
    )
    (net (code "34") (name "OLED_SCL") (class "Default")
      (node (ref "J4") (pin "3") (pinfunction "3_3") (pintype "unspecified"))
      (node (ref "R37") (pin "2") (pinfunction "2_2") (pintype "input"))
      (node (ref "U1") (pin "25") (pinfunction "PB12_25") (pintype "unspecified"))
    )
    (net (code "35") (name "OLED_SDA") (class "Default")
      (node (ref "J4") (pin "4") (pinfunction "4_4") (pintype "unspecified"))
      (node (ref "R38") (pin "2") (pinfunction "2_2") (pintype "input"))
      (node (ref "U1") (pin "26") (pinfunction "PB13_26") (pintype "unspecified"))
    )
    (net (code "36") (name "PWR_EN") (class "Default")
      (node (ref "J1") (pin "4") (pinfunction "4_4") (pintype "unspecified"))
      (node (ref "R27") (pin "2") (pinfunction "2_2") (pintype "input"))
    )
    (net (code "37") (name "RING") (class "Default")
      (node (ref "R1") (pin "2") (pinfunction "2_2") (pintype "input"))
      (node (ref "U1") (pin "15") (pinfunction "PA5_15") (pintype "unspecified"))
    )
    (net (code "38") (name "STM32_RXD1") (class "Default")
      (node (ref "R23") (pin "1") (pinfunction "1_1") (pintype "input"))
      (node (ref "U1") (pin "31") (pinfunction "PA10_31") (pintype "unspecified"))
    )
    (net (code "39") (name "STM32_RXD2") (class "Default")
      (node (ref "R20") (pin "2") (pinfunction "2_2") (pintype "input"))
      (node (ref "U1") (pin "13") (pinfunction "PA3_13") (pintype "unspecified"))
    )
    (net (code "40") (name "STM32_TXD1") (class "Default")
      (node (ref "R22") (pin "1") (pinfunction "1_1") (pintype "input"))
      (node (ref "U1") (pin "30") (pinfunction "PA9_30") (pintype "unspecified"))
    )
    (net (code "41") (name "STM32_TXD2") (class "Default")
      (node (ref "R21") (pin "2") (pinfunction "2_2") (pintype "input"))
      (node (ref "U1") (pin "12") (pinfunction "PA2_12") (pintype "unspecified"))
    )
    (net (code "42") (name "SWCLK") (class "Default")
      (node (ref "R19") (pin "1") (pinfunction "1_1") (pintype "input"))
      (node (ref "U1") (pin "37") (pinfunction "PA14_37") (pintype "unspecified"))
    )
    (net (code "43") (name "SWDIO") (class "Default")
      (node (ref "R18") (pin "1") (pinfunction "1_1") (pintype "input"))
      (node (ref "U1") (pin "34") (pinfunction "PA13_34") (pintype "unspecified"))
    )
    (net (code "44") (name "TFT_BLK") (class "Default")
      (node (ref "J2") (pin "14") (pinfunction "14_14") (pintype "unspecified"))
      (node (ref "J3") (pin "8") (pinfunction "8_8") (pintype "unspecified"))
    )
    (net (code "45") (name "TFT_CS") (class "Default")
      (node (ref "J2") (pin "3") (pinfunction "3_3") (pintype "unspecified"))
      (node (ref "J3") (pin "7") (pinfunction "7_7") (pintype "unspecified"))
    )
    (net (code "46") (name "TFT_DC") (class "Default")
      (node (ref "J2") (pin "4") (pinfunction "4_4") (pintype "unspecified"))
      (node (ref "J3") (pin "6") (pinfunction "6_6") (pintype "unspecified"))
    )
    (net (code "47") (name "TFT_K1") (class "Default")
      (node (ref "J2") (pin "11") (pinfunction "11_11") (pintype "unspecified"))
      (node (ref "J3") (pin "12") (pinfunction "12_12") (pintype "unspecified"))
    )
    (net (code "48") (name "TFT_K2") (class "Default")
      (node (ref "J2") (pin "10") (pinfunction "10_10") (pintype "unspecified"))
      (node (ref "J3") (pin "11") (pinfunction "11_11") (pintype "unspecified"))
    )
    (net (code "49") (name "TFT_K3") (class "Default")
      (node (ref "J2") (pin "8") (pinfunction "8_8") (pintype "unspecified"))
      (node (ref "J3") (pin "10") (pinfunction "10_10") (pintype "unspecified"))
    )
    (net (code "50") (name "TFT_K4") (class "Default")
      (node (ref "J2") (pin "7") (pinfunction "7_7") (pintype "unspecified"))
      (node (ref "J3") (pin "9") (pinfunction "9_9") (pintype "unspecified"))
    )
    (net (code "51") (name "TFT_RST") (class "Default")
      (node (ref "J2") (pin "5") (pinfunction "5_5") (pintype "unspecified"))
      (node (ref "J3") (pin "5") (pinfunction "5_5") (pintype "unspecified"))
    )
    (net (code "52") (name "TFT_SCL") (class "Default")
      (node (ref "J2") (pin "9") (pinfunction "9_9") (pintype "unspecified"))
      (node (ref "J3") (pin "3") (pinfunction "3_3") (pintype "unspecified"))
    )
    (net (code "53") (name "TFT_SDA") (class "Default")
      (node (ref "J2") (pin "15") (pinfunction "15_15") (pintype "unspecified"))
      (node (ref "J3") (pin "4") (pinfunction "4_4") (pintype "unspecified"))
    )
    (net (code "54") (name "TURN_LIGHT") (class "Default")
      (node (ref "J2") (pin "6") (pinfunction "6_6") (pintype "unspecified"))
      (node (ref "U1") (pin "18") (pinfunction "PB0_18") (pintype "unspecified"))
    )
    (net (code "55") (name "USB_DET") (class "Default")
      (node (ref "C19") (pin "2") (pinfunction "2_2") (pintype "unspecified"))
      (node (ref "J1") (pin "5") (pinfunction "5_5") (pintype "unspecified"))
      (node (ref "R24") (pin "2") (pinfunction "2_2") (pintype "unspecified"))
      (node (ref "R25") (pin "1") (pinfunction "1_1") (pintype "input"))
    )
    (net (code "56") (name "V33") (class "Default")
      (node (ref "C5") (pin "2") (pinfunction "2_2") (pintype "unspecified"))
      (node (ref "Q3") (pin "2") (pinfunction "S_2") (pintype "unspecified"))
      (node (ref "R13") (pin "1") (pinfunction "1_1") (pintype "input"))
      (node (ref "R14") (pin "1") (pinfunction "1_1") (pintype "input"))
      (node (ref "R26") (pin "2") (pinfunction "2_2") (pintype "input"))
      (node (ref "U4") (pin "1") (pinfunction "VOUT_1") (pintype "unspecified"))
    )
    (net (code "57") (name "VBAT") (class "Default")
      (node (ref "C7") (pin "2") (pinfunction "2_2") (pintype "input"))
      (node (ref "CN1") (pin "1") (pinfunction "1_1") (pintype "unspecified"))
      (node (ref "D2") (pin "2") (pinfunction "+_2") (pintype "unspecified"))
      (node (ref "Q2") (pin "3") (pinfunction "D_3") (pintype "unspecified"))
      (node (ref "R12") (pin "2") (pinfunction "2_2") (pintype "input"))
      (node (ref "U10") (pin "3") (pinfunction "BAT_3") (pintype "unspecified"))
    )
    (net (code "58") (name "VBUS") (class "Default")
      (node (ref "C17") (pin "2") (pinfunction "2_2") (pintype "unspecified"))
      (node (ref "C6") (pin "2") (pinfunction "2_2") (pintype "unspecified"))
      (node (ref "D1") (pin "1") (pinfunction "-_1") (pintype "unspecified"))
      (node (ref "D2") (pin "1") (pinfunction "-_1") (pintype "unspecified"))
      (node (ref "Q2") (pin "2") (pinfunction "S_2") (pintype "unspecified"))
      (node (ref "R16") (pin "2") (pinfunction "2_2") (pintype "input"))
      (node (ref "R40") (pin "1") (pinfunction "1_1") (pintype "input"))
      (node (ref "U4") (pin "8") (pinfunction "VIN_8") (pintype "unspecified"))
    )
    (net (code "59") (name "VCC3V3") (class "Default")
      (node (ref "C10") (pin "1") (pinfunction "1_1") (pintype "unspecified"))
      (node (ref "C11") (pin "1") (pinfunction "1_1") (pintype "unspecified"))
      (node (ref "C12") (pin "1") (pinfunction "1_1") (pintype "unspecified"))
      (node (ref "C13") (pin "1") (pinfunction "1_1") (pintype "unspecified"))
      (node (ref "C14") (pin "2") (pinfunction "2_2") (pintype "unspecified"))
      (node (ref "C16") (pin "2") (pinfunction "2_2") (pintype "input"))
      (node (ref "C18") (pin "1") (pinfunction "1_1") (pintype "input"))
      (node (ref "C9") (pin "2") (pinfunction "2_2") (pintype "input"))
      (node (ref "D4") (pin "1") (pinfunction "-_1") (pintype "unspecified"))
      (node (ref "J3") (pin "2") (pinfunction "2_2") (pintype "unspecified"))
      (node (ref "J4") (pin "2") (pinfunction "2_2") (pintype "unspecified"))
      (node (ref "Q3") (pin "3") (pinfunction "D_3") (pintype "unspecified"))
      (node (ref "R14") (pin "2") (pinfunction "2_2") (pintype "input"))
      (node (ref "R15") (pin "1") (pinfunction "1_1") (pintype "unspecified"))
      (node (ref "R3") (pin "2") (pinfunction "2_2") (pintype "input"))
      (node (ref "R32") (pin "1") (pinfunction "1_1") (pintype "input"))
      (node (ref "R33") (pin "1") (pinfunction "1_1") (pintype "input"))
      (node (ref "R34") (pin "1") (pinfunction "1_1") (pintype "input"))
      (node (ref "R36") (pin "2") (pinfunction "2_2") (pintype "input"))
      (node (ref "R37") (pin "1") (pinfunction "1_1") (pintype "input"))
      (node (ref "R38") (pin "1") (pinfunction "1_1") (pintype "input"))
      (node (ref "U1") (pin "1") (pinfunction "VBAT_1") (pintype "unspecified"))
      (node (ref "U1") (pin "24") (pinfunction "VDD_1_24") (pintype "unspecified"))
      (node (ref "U1") (pin "36") (pinfunction "VDD_2_36") (pintype "unspecified"))
      (node (ref "U1") (pin "48") (pinfunction "VDD_3_48") (pintype "unspecified"))
      (node (ref "U1") (pin "9") (pinfunction "VDDA_9") (pintype "unspecified"))
    )
    (net (code "60") (name "VDD3V3") (class "Default")
      (node (ref "C20") (pin "2") (pinfunction "2_2") (pintype "unspecified"))
      (node (ref "C8") (pin "2") (pinfunction "2_2") (pintype "input"))
      (node (ref "J2") (pin "1") (pinfunction "1_1") (pintype "unspecified"))
      (node (ref "R13") (pin "2") (pinfunction "2_2") (pintype "input"))
      (node (ref "R28") (pin "2") (pinfunction "2_2") (pintype "input"))
      (node (ref "R29") (pin "2") (pinfunction "2_2") (pintype "input"))
      (node (ref "R31") (pin "1") (pinfunction "1_1") (pintype "input"))
      (node (ref "R35") (pin "2") (pinfunction "2_2") (pintype "input"))
      (node (ref "R6") (pin "2") (pinfunction "2_2") (pintype "input"))
      (node (ref "U2") (pin "3") (pinfunction "VDD_3") (pintype "unspecified"))
    )
    (net (code "61") (name "VIN") (class "Default")
      (node (ref "C3") (pin "2") (pinfunction "2_2") (pintype "unspecified"))
      (node (ref "D1") (pin "2") (pinfunction "+_2") (pintype "unspecified"))
      (node (ref "J1") (pin "1") (pinfunction "1_1") (pintype "unspecified"))
      (node (ref "LED1") (pin "1") (pinfunction "+_1") (pintype "unspecified"))
      (node (ref "R25") (pin "2") (pinfunction "2_2") (pintype "input"))
      (node (ref "R8") (pin "2") (pinfunction "2_2") (pintype "input"))
      (node (ref "U10") (pin "4") (pinfunction "VCC_4") (pintype "unspecified"))
    )
    (net (code "62") (name "unconnected-(J1-Pad3)") (class "Default")
      (node (ref "J1") (pin "3") (pinfunction "3_3") (pintype "unspecified+no_connect"))
    )
    (net (code "63") (name "unconnected-(J1-Pad13)") (class "Default")
      (node (ref "J1") (pin "13") (pinfunction "13_13") (pintype "unspecified+no_connect"))
    )
    (net (code "64") (name "unconnected-(J1-Pad14)") (class "Default")
      (node (ref "J1") (pin "14") (pinfunction "14_14") (pintype "unspecified+no_connect"))
    )
    (net (code "65") (name "unconnected-(J2-Pad12)") (class "Default")
      (node (ref "J2") (pin "12") (pinfunction "12_12") (pintype "unspecified"))
    )
    (net (code "66") (name "unconnected-(J2-Pad13)") (class "Default")
      (node (ref "J2") (pin "13") (pinfunction "13_13") (pintype "unspecified"))
    )
    (net (code "67") (name "unconnected-(J5-Pad5)") (class "Default")
      (node (ref "J5") (pin "5") (pinfunction "5_5") (pintype "unspecified"))
    )
    (net (code "68") (name "unconnected-(J5-Pad6)") (class "Default")
      (node (ref "J5") (pin "6") (pinfunction "6_6") (pintype "unspecified"))
    )
    (net (code "69") (name "unconnected-(J5-Pad7)") (class "Default")
      (node (ref "J5") (pin "7") (pinfunction "7_7") (pintype "unspecified"))
    )
    (net (code "70") (name "unconnected-(U1-PA0-WKUP-Pad10)") (class "Default")
      (node (ref "U1") (pin "10") (pinfunction "PA0-WKUP_10") (pintype "unspecified"))
    )
    (net (code "71") (name "unconnected-(U1-PA1-Pad11)") (class "Default")
      (node (ref "U1") (pin "11") (pinfunction "PA1_11") (pintype "unspecified"))
    )
    (net (code "72") (name "unconnected-(U1-PA4-Pad14)") (class "Default")
      (node (ref "U1") (pin "14") (pinfunction "PA4_14") (pintype "unspecified"))
    )
    (net (code "73") (name "unconnected-(U1-PA6-Pad16)") (class "Default")
      (node (ref "U1") (pin "16") (pinfunction "PA6_16") (pintype "unspecified"))
    )
    (net (code "74") (name "unconnected-(U1-PA7-Pad17)") (class "Default")
      (node (ref "U1") (pin "17") (pinfunction "PA7_17") (pintype "unspecified"))
    )
    (net (code "75") (name "unconnected-(U1-PA8-Pad29)") (class "Default")
      (node (ref "U1") (pin "29") (pinfunction "PA8_29") (pintype "unspecified"))
    )
    (net (code "76") (name "unconnected-(U1-PA11-Pad32)") (class "Default")
      (node (ref "U1") (pin "32") (pinfunction "PA11_32") (pintype "unspecified"))
    )
    (net (code "77") (name "unconnected-(U1-PA12-Pad33)") (class "Default")
      (node (ref "U1") (pin "33") (pinfunction "PA12_33") (pintype "unspecified"))
    )
    (net (code "78") (name "unconnected-(U1-PA15-Pad38)") (class "Default")
      (node (ref "U1") (pin "38") (pinfunction "PA15_38") (pintype "unspecified"))
    )
    (net (code "79") (name "unconnected-(U1-PB1-Pad19)") (class "Default")
      (node (ref "U1") (pin "19") (pinfunction "PB1_19") (pintype "unspecified"))
    )
    (net (code "80") (name "unconnected-(U1-PB2-Pad20)") (class "Default")
      (node (ref "U1") (pin "20") (pinfunction "PB2_20") (pintype "unspecified"))
    )
    (net (code "81") (name "unconnected-(U1-PB3-Pad39)") (class "Default")
      (node (ref "U1") (pin "39") (pinfunction "PB3_39") (pintype "unspecified"))
    )
    (net (code "82") (name "unconnected-(U1-PB4-Pad40)") (class "Default")
      (node (ref "U1") (pin "40") (pinfunction "PB4_40") (pintype "unspecified"))
    )
    (net (code "83") (name "unconnected-(U1-PB5-Pad41)") (class "Default")
      (node (ref "U1") (pin "41") (pinfunction "PB5_41") (pintype "unspecified"))
    )
    (net (code "84") (name "unconnected-(U1-PB6-Pad42)") (class "Default")
      (node (ref "U1") (pin "42") (pinfunction "PB6_42") (pintype "unspecified"))
    )
    (net (code "85") (name "unconnected-(U1-PB7-Pad43)") (class "Default")
      (node (ref "U1") (pin "43") (pinfunction "PB7_43") (pintype "unspecified"))
    )
    (net (code "86") (name "unconnected-(U1-PB8-Pad45)") (class "Default")
      (node (ref "U1") (pin "45") (pinfunction "PB8_45") (pintype "unspecified"))
    )
    (net (code "87") (name "unconnected-(U1-PB9-Pad46)") (class "Default")
      (node (ref "U1") (pin "46") (pinfunction "PB9_46") (pintype "unspecified"))
    )
    (net (code "88") (name "unconnected-(U1-PB14-Pad27)") (class "Default")
      (node (ref "U1") (pin "27") (pinfunction "PB14_27") (pintype "unspecified"))
    )
    (net (code "89") (name "unconnected-(U1-PB15-Pad28)") (class "Default")
      (node (ref "U1") (pin "28") (pinfunction "PB15_28") (pintype "unspecified"))
    )
    (net (code "90") (name "unconnected-(U1-PC13-TAMPER-RTC-Pad2)") (class "Default")
      (node (ref "U1") (pin "2") (pinfunction "PC13-TAMPER-RTC_2") (pintype "unspecified"))
    )
    (net (code "91") (name "unconnected-(U1-PC14-OSC32_IN-Pad3)") (class "Default")
      (node (ref "U1") (pin "3") (pinfunction "PC14-OSC32_IN_3") (pintype "unspecified"))
    )
    (net (code "92") (name "unconnected-(U1-PC15-OSC32_OUT-Pad4)") (class "Default")
      (node (ref "U1") (pin "4") (pinfunction "PC15-OSC32_OUT_4") (pintype "unspecified"))
    )
    (net (code "93") (name "unconnected-(U1-PD0-OSC_IN-Pad5)") (class "Default")
      (node (ref "U1") (pin "5") (pinfunction "PD0-OSC_IN_5") (pintype "unspecified"))
    )
    (net (code "94") (name "unconnected-(U1-PD1-OSC_OUT-Pad6)") (class "Default")
      (node (ref "U1") (pin "6") (pinfunction "PD1-OSC_OUT_6") (pintype "unspecified"))
    )
    (net (code "95") (name "unconnected-(U4-NC-Pad3)") (class "Default")
      (node (ref "U4") (pin "3") (pinfunction "NC_3") (pintype "unspecified"))
    )
    (net (code "96") (name "unconnected-(U4-NC-Pad5)") (class "Default")
      (node (ref "U4") (pin "5") (pinfunction "NC_5") (pintype "unspecified"))
    )
    (net (code "97") (name "unconnected-(U4-NC-Pad6)") (class "Default")
      (node (ref "U4") (pin "6") (pinfunction "NC_6") (pintype "unspecified"))
    )
    (net (code "98") (name "unconnected-(U4-NC-Pad7)") (class "Default")
      (node (ref "U4") (pin "7") (pinfunction "NC_7") (pintype "unspecified"))
    )
  )
)
